# 2layer_v2.net
KiCad netlist of a schematic drawn in EAGLE
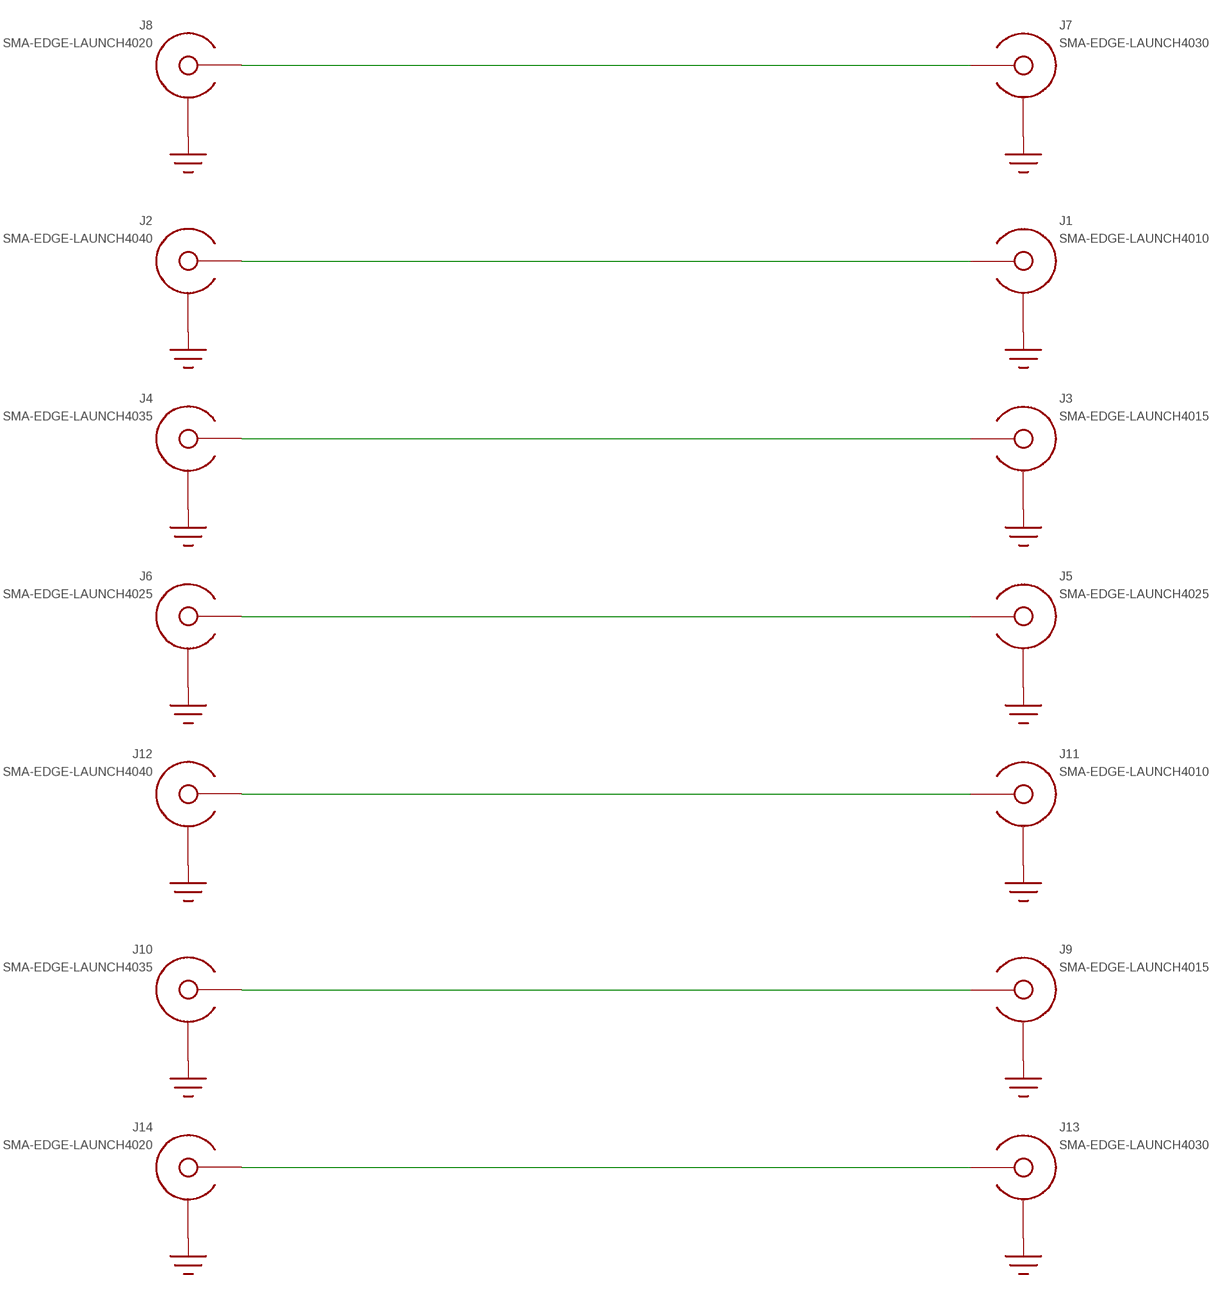
[diagram p0: schematic, sheet 1]

(export (version "E")
  (design (tool "Eeschema 10.0.6"))
  (components
    (comp (ref "J1")
      (value "SMA-EDGE-LAUNCH4010")
      (footprint "eagle-import:SMA_EDGE_LAUNCH_2L_4010")
      (libsource (lib "eagle-import") (part "SMA-EDGE-LAUNCH4010"))
    )
    (comp (ref "J2")
      (value "SMA-EDGE-LAUNCH4040")
      (footprint "eagle-import:SMA_EDGE_LAUNCH_2L_4040")
      (libsource (lib "eagle-import") (part "SMA-EDGE-LAUNCH4040"))
    )
    (comp (ref "J3")
      (value "SMA-EDGE-LAUNCH4015")
      (footprint "eagle-import:SMA_EDGE_LAUNCH_2L_4015")
      (libsource (lib "eagle-import") (part "SMA-EDGE-LAUNCH4015"))
    )
    (comp (ref "J4")
      (value "SMA-EDGE-LAUNCH4035")
      (footprint "eagle-import:SMA_EDGE_LAUNCH_2L_4035")
      (libsource (lib "eagle-import") (part "SMA-EDGE-LAUNCH4035"))
    )
    (comp (ref "J5")
      (value "SMA-EDGE-LAUNCH4025")
      (footprint "eagle-import:SMA_EDGE_LAUNCH_2L_4025")
      (libsource (lib "eagle-import") (part "SMA-EDGE-LAUNCH4025"))
    )
    (comp (ref "J6")
      (value "SMA-EDGE-LAUNCH4025")
      (footprint "eagle-import:SMA_EDGE_LAUNCH_2L_4025")
      (libsource (lib "eagle-import") (part "SMA-EDGE-LAUNCH4025"))
    )
    (comp (ref "J7")
      (value "SMA-EDGE-LAUNCH4030")
      (footprint "eagle-import:SMA_EDGE_LAUNCH_2L_4030")
      (libsource (lib "eagle-import") (part "SMA-EDGE-LAUNCH4030"))
    )
    (comp (ref "J8")
      (value "SMA-EDGE-LAUNCH4020")
      (footprint "eagle-import:SMA_EDGE_LAUNCH_2L_4020")
      (libsource (lib "eagle-import") (part "SMA-EDGE-LAUNCH4020"))
    )
    (comp (ref "J9")
      (value "SMA-EDGE-LAUNCH4015")
      (footprint "eagle-import:SMA_EDGE_LAUNCH_2L_4015")
      (libsource (lib "eagle-import") (part "SMA-EDGE-LAUNCH4015"))
    )
    (comp (ref "J10")
      (value "SMA-EDGE-LAUNCH4035")
      (footprint "eagle-import:SMA_EDGE_LAUNCH_2L_4035")
      (libsource (lib "eagle-import") (part "SMA-EDGE-LAUNCH4035"))
    )
    (comp (ref "J11")
      (value "SMA-EDGE-LAUNCH4010")
      (footprint "eagle-import:SMA_EDGE_LAUNCH_2L_4010")
      (libsource (lib "eagle-import") (part "SMA-EDGE-LAUNCH4010"))
    )
    (comp (ref "J12")
      (value "SMA-EDGE-LAUNCH4040")
      (footprint "eagle-import:SMA_EDGE_LAUNCH_2L_4040")
      (libsource (lib "eagle-import") (part "SMA-EDGE-LAUNCH4040"))
    )
    (comp (ref "J13")
      (value "SMA-EDGE-LAUNCH4030")
      (footprint "eagle-import:SMA_EDGE_LAUNCH_2L_4030")
      (libsource (lib "eagle-import") (part "SMA-EDGE-LAUNCH4030"))
    )
    (comp (ref "J14")
      (value "SMA-EDGE-LAUNCH4020")
      (footprint "eagle-import:SMA_EDGE_LAUNCH_2L_4020")
      (libsource (lib "eagle-import") (part "SMA-EDGE-LAUNCH4020"))
    )
  )
  (nets
    (net (code "1") (name "GND") (class "Default")
      (node (ref "J1") (pin "BOTTOM_GND") (pinfunction "SHIELD_BOTTOM_GND") (pintype "bidirectional"))
      (node (ref "J1") (pin "GND@1") (pinfunction "SHIELD_GND@1") (pintype "bidirectional"))
      (node (ref "J1") (pin "GND@11") (pinfunction "SHIELD_GND@11") (pintype "bidirectional"))
      (node (ref "J1") (pin "GND@12") (pinfunction "SHIELD_GND@12") (pintype "bidirectional"))
      (node (ref "J1") (pin "GND@14") (pinfunction "SHIELD_GND@14") (pintype "bidirectional"))
      (node (ref "J1") (pin "GND@15") (pinfunction "SHIELD_GND@15") (pintype "bidirectional"))
      (node (ref "J1") (pin "GND@16") (pinfunction "SHIELD_GND@16") (pintype "bidirectional"))
      (node (ref "J1") (pin "GND@17") (pinfunction "SHIELD_GND@17") (pintype "bidirectional"))
      (node (ref "J1") (pin "GND@2") (pinfunction "SHIELD_GND@2") (pintype "bidirectional"))
      (node (ref "J1") (pin "GND@3") (pinfunction "SHIELD_GND@3") (pintype "bidirectional"))
      (node (ref "J1") (pin "GND@4") (pinfunction "SHIELD_GND@4") (pintype "bidirectional"))
      (node (ref "J1") (pin "GND@5") (pinfunction "SHIELD_GND@5") (pintype "bidirectional"))
      (node (ref "J1") (pin "GND@6") (pinfunction "SHIELD_GND@6") (pintype "bidirectional"))
      (node (ref "J1") (pin "GND@7") (pinfunction "SHIELD_GND@7") (pintype "bidirectional"))
      (node (ref "J1") (pin "GND@8") (pinfunction "SHIELD_GND@8") (pintype "bidirectional"))
      (node (ref "J1") (pin "GND_PAD1") (pinfunction "SHIELD_GND_PAD1") (pintype "bidirectional"))
      (node (ref "J1") (pin "GND_PAD2") (pinfunction "SHIELD_GND_PAD2") (pintype "bidirectional"))
      (node (ref "J10") (pin "BOTTOM_GND") (pinfunction "SHIELD_BOTTOM_GND") (pintype "bidirectional"))
      (node (ref "J10") (pin "GND@1") (pinfunction "SHIELD_GND@1") (pintype "bidirectional"))
      (node (ref "J10") (pin "GND@11") (pinfunction "SHIELD_GND@11") (pintype "bidirectional"))
      (node (ref "J10") (pin "GND@12") (pinfunction "SHIELD_GND@12") (pintype "bidirectional"))
      (node (ref "J10") (pin "GND@14") (pinfunction "SHIELD_GND@14") (pintype "bidirectional"))
      (node (ref "J10") (pin "GND@15") (pinfunction "SHIELD_GND@15") (pintype "bidirectional"))
      (node (ref "J10") (pin "GND@16") (pinfunction "SHIELD_GND@16") (pintype "bidirectional"))
      (node (ref "J10") (pin "GND@17") (pinfunction "SHIELD_GND@17") (pintype "bidirectional"))
      (node (ref "J10") (pin "GND@2") (pinfunction "SHIELD_GND@2") (pintype "bidirectional"))
      (node (ref "J10") (pin "GND@3") (pinfunction "SHIELD_GND@3") (pintype "bidirectional"))
      (node (ref "J10") (pin "GND@4") (pinfunction "SHIELD_GND@4") (pintype "bidirectional"))
      (node (ref "J10") (pin "GND@5") (pinfunction "SHIELD_GND@5") (pintype "bidirectional"))
      (node (ref "J10") (pin "GND@6") (pinfunction "SHIELD_GND@6") (pintype "bidirectional"))
      (node (ref "J10") (pin "GND@7") (pinfunction "SHIELD_GND@7") (pintype "bidirectional"))
      (node (ref "J10") (pin "GND@8") (pinfunction "SHIELD_GND@8") (pintype "bidirectional"))
      (node (ref "J10") (pin "GND_PAD1") (pinfunction "SHIELD_GND_PAD1") (pintype "bidirectional"))
      (node (ref "J10") (pin "GND_PAD2") (pinfunction "SHIELD_GND_PAD2") (pintype "bidirectional"))
      (node (ref "J11") (pin "BOTTOM_GND") (pinfunction "SHIELD_BOTTOM_GND") (pintype "bidirectional"))
      (node (ref "J11") (pin "GND@1") (pinfunction "SHIELD_GND@1") (pintype "bidirectional"))
      (node (ref "J11") (pin "GND@11") (pinfunction "SHIELD_GND@11") (pintype "bidirectional"))
      (node (ref "J11") (pin "GND@12") (pinfunction "SHIELD_GND@12") (pintype "bidirectional"))
      (node (ref "J11") (pin "GND@14") (pinfunction "SHIELD_GND@14") (pintype "bidirectional"))
      (node (ref "J11") (pin "GND@15") (pinfunction "SHIELD_GND@15") (pintype "bidirectional"))
      (node (ref "J11") (pin "GND@16") (pinfunction "SHIELD_GND@16") (pintype "bidirectional"))
      (node (ref "J11") (pin "GND@17") (pinfunction "SHIELD_GND@17") (pintype "bidirectional"))
      (node (ref "J11") (pin "GND@2") (pinfunction "SHIELD_GND@2") (pintype "bidirectional"))
      (node (ref "J11") (pin "GND@3") (pinfunction "SHIELD_GND@3") (pintype "bidirectional"))
      (node (ref "J11") (pin "GND@4") (pinfunction "SHIELD_GND@4") (pintype "bidirectional"))
      (node (ref "J11") (pin "GND@5") (pinfunction "SHIELD_GND@5") (pintype "bidirectional"))
      (node (ref "J11") (pin "GND@6") (pinfunction "SHIELD_GND@6") (pintype "bidirectional"))
      (node (ref "J11") (pin "GND@7") (pinfunction "SHIELD_GND@7") (pintype "bidirectional"))
      (node (ref "J11") (pin "GND@8") (pinfunction "SHIELD_GND@8") (pintype "bidirectional"))
      (node (ref "J11") (pin "GND_PAD1") (pinfunction "SHIELD_GND_PAD1") (pintype "bidirectional"))
      (node (ref "J11") (pin "GND_PAD2") (pinfunction "SHIELD_GND_PAD2") (pintype "bidirectional"))
      (node (ref "J12") (pin "BOTTOM_GND") (pinfunction "SHIELD_BOTTOM_GND") (pintype "bidirectional"))
      (node (ref "J12") (pin "GND@1") (pinfunction "SHIELD_GND@1") (pintype "bidirectional"))
      (node (ref "J12") (pin "GND@11") (pinfunction "SHIELD_GND@11") (pintype "bidirectional"))
      (node (ref "J12") (pin "GND@12") (pinfunction "SHIELD_GND@12") (pintype "bidirectional"))
      (node (ref "J12") (pin "GND@14") (pinfunction "SHIELD_GND@14") (pintype "bidirectional"))
      (node (ref "J12") (pin "GND@15") (pinfunction "SHIELD_GND@15") (pintype "bidirectional"))
      (node (ref "J12") (pin "GND@16") (pinfunction "SHIELD_GND@16") (pintype "bidirectional"))
      (node (ref "J12") (pin "GND@17") (pinfunction "SHIELD_GND@17") (pintype "bidirectional"))
      (node (ref "J12") (pin "GND@2") (pinfunction "SHIELD_GND@2") (pintype "bidirectional"))
      (node (ref "J12") (pin "GND@3") (pinfunction "SHIELD_GND@3") (pintype "bidirectional"))
      (node (ref "J12") (pin "GND@4") (pinfunction "SHIELD_GND@4") (pintype "bidirectional"))
      (node (ref "J12") (pin "GND@5") (pinfunction "SHIELD_GND@5") (pintype "bidirectional"))
      (node (ref "J12") (pin "GND@6") (pinfunction "SHIELD_GND@6") (pintype "bidirectional"))
      (node (ref "J12") (pin "GND@7") (pinfunction "SHIELD_GND@7") (pintype "bidirectional"))
      (node (ref "J12") (pin "GND@8") (pinfunction "SHIELD_GND@8") (pintype "bidirectional"))
      (node (ref "J12") (pin "GND_PAD1") (pinfunction "SHIELD_GND_PAD1") (pintype "bidirectional"))
      (node (ref "J12") (pin "GND_PAD2") (pinfunction "SHIELD_GND_PAD2") (pintype "bidirectional"))
      (node (ref "J13") (pin "BOTTOM_GND") (pinfunction "SHIELD_BOTTOM_GND") (pintype "bidirectional"))
      (node (ref "J13") (pin "GND@1") (pinfunction "SHIELD_GND@1") (pintype "bidirectional"))
      (node (ref "J13") (pin "GND@11") (pinfunction "SHIELD_GND@11") (pintype "bidirectional"))
      (node (ref "J13") (pin "GND@12") (pinfunction "SHIELD_GND@12") (pintype "bidirectional"))
      (node (ref "J13") (pin "GND@14") (pinfunction "SHIELD_GND@14") (pintype "bidirectional"))
      (node (ref "J13") (pin "GND@15") (pinfunction "SHIELD_GND@15") (pintype "bidirectional"))
      (node (ref "J13") (pin "GND@16") (pinfunction "SHIELD_GND@16") (pintype "bidirectional"))
      (node (ref "J13") (pin "GND@17") (pinfunction "SHIELD_GND@17") (pintype "bidirectional"))
      (node (ref "J13") (pin "GND@2") (pinfunction "SHIELD_GND@2") (pintype "bidirectional"))
      (node (ref "J13") (pin "GND@3") (pinfunction "SHIELD_GND@3") (pintype "bidirectional"))
      (node (ref "J13") (pin "GND@4") (pinfunction "SHIELD_GND@4") (pintype "bidirectional"))
      (node (ref "J13") (pin "GND@5") (pinfunction "SHIELD_GND@5") (pintype "bidirectional"))
      (node (ref "J13") (pin "GND@6") (pinfunction "SHIELD_GND@6") (pintype "bidirectional"))
      (node (ref "J13") (pin "GND@7") (pinfunction "SHIELD_GND@7") (pintype "bidirectional"))
      (node (ref "J13") (pin "GND@8") (pinfunction "SHIELD_GND@8") (pintype "bidirectional"))
      (node (ref "J13") (pin "GND_PAD1") (pinfunction "SHIELD_GND_PAD1") (pintype "bidirectional"))
      (node (ref "J13") (pin "GND_PAD2") (pinfunction "SHIELD_GND_PAD2") (pintype "bidirectional"))
      (node (ref "J14") (pin "BOTTOM_GND") (pinfunction "SHIELD_BOTTOM_GND") (pintype "bidirectional"))
      (node (ref "J14") (pin "GND@1") (pinfunction "SHIELD_GND@1") (pintype "bidirectional"))
      (node (ref "J14") (pin "GND@11") (pinfunction "SHIELD_GND@11") (pintype "bidirectional"))
      (node (ref "J14") (pin "GND@12") (pinfunction "SHIELD_GND@12") (pintype "bidirectional"))
      (node (ref "J14") (pin "GND@14") (pinfunction "SHIELD_GND@14") (pintype "bidirectional"))
      (node (ref "J14") (pin "GND@15") (pinfunction "SHIELD_GND@15") (pintype "bidirectional"))
      (node (ref "J14") (pin "GND@16") (pinfunction "SHIELD_GND@16") (pintype "bidirectional"))
      (node (ref "J14") (pin "GND@17") (pinfunction "SHIELD_GND@17") (pintype "bidirectional"))
      (node (ref "J14") (pin "GND@2") (pinfunction "SHIELD_GND@2") (pintype "bidirectional"))
      (node (ref "J14") (pin "GND@3") (pinfunction "SHIELD_GND@3") (pintype "bidirectional"))
      (node (ref "J14") (pin "GND@4") (pinfunction "SHIELD_GND@4") (pintype "bidirectional"))
      (node (ref "J14") (pin "GND@5") (pinfunction "SHIELD_GND@5") (pintype "bidirectional"))
      (node (ref "J14") (pin "GND@6") (pinfunction "SHIELD_GND@6") (pintype "bidirectional"))
      (node (ref "J14") (pin "GND@7") (pinfunction "SHIELD_GND@7") (pintype "bidirectional"))
      (node (ref "J14") (pin "GND@8") (pinfunction "SHIELD_GND@8") (pintype "bidirectional"))
      (node (ref "J14") (pin "GND_PAD1") (pinfunction "SHIELD_GND_PAD1") (pintype "bidirectional"))
      (node (ref "J14") (pin "GND_PAD2") (pinfunction "SHIELD_GND_PAD2") (pintype "bidirectional"))
      (node (ref "J2") (pin "BOTTOM_GND") (pinfunction "SHIELD_BOTTOM_GND") (pintype "bidirectional"))
      (node (ref "J2") (pin "GND@1") (pinfunction "SHIELD_GND@1") (pintype "bidirectional"))
      (node (ref "J2") (pin "GND@11") (pinfunction "SHIELD_GND@11") (pintype "bidirectional"))
      (node (ref "J2") (pin "GND@12") (pinfunction "SHIELD_GND@12") (pintype "bidirectional"))
      (node (ref "J2") (pin "GND@14") (pinfunction "SHIELD_GND@14") (pintype "bidirectional"))
      (node (ref "J2") (pin "GND@15") (pinfunction "SHIELD_GND@15") (pintype "bidirectional"))
      (node (ref "J2") (pin "GND@16") (pinfunction "SHIELD_GND@16") (pintype "bidirectional"))
      (node (ref "J2") (pin "GND@17") (pinfunction "SHIELD_GND@17") (pintype "bidirectional"))
      (node (ref "J2") (pin "GND@2") (pinfunction "SHIELD_GND@2") (pintype "bidirectional"))
      (node (ref "J2") (pin "GND@3") (pinfunction "SHIELD_GND@3") (pintype "bidirectional"))
      (node (ref "J2") (pin "GND@4") (pinfunction "SHIELD_GND@4") (pintype "bidirectional"))
      (node (ref "J2") (pin "GND@5") (pinfunction "SHIELD_GND@5") (pintype "bidirectional"))
      (node (ref "J2") (pin "GND@6") (pinfunction "SHIELD_GND@6") (pintype "bidirectional"))
      (node (ref "J2") (pin "GND@7") (pinfunction "SHIELD_GND@7") (pintype "bidirectional"))
      (node (ref "J2") (pin "GND@8") (pinfunction "SHIELD_GND@8") (pintype "bidirectional"))
      (node (ref "J2") (pin "GND_PAD1") (pinfunction "SHIELD_GND_PAD1") (pintype "bidirectional"))
      (node (ref "J2") (pin "GND_PAD2") (pinfunction "SHIELD_GND_PAD2") (pintype "bidirectional"))
      (node (ref "J3") (pin "BOTTOM_GND") (pinfunction "SHIELD_BOTTOM_GND") (pintype "bidirectional"))
      (node (ref "J3") (pin "GND@1") (pinfunction "SHIELD_GND@1") (pintype "bidirectional"))
      (node (ref "J3") (pin "GND@11") (pinfunction "SHIELD_GND@11") (pintype "bidirectional"))
      (node (ref "J3") (pin "GND@12") (pinfunction "SHIELD_GND@12") (pintype "bidirectional"))
      (node (ref "J3") (pin "GND@14") (pinfunction "SHIELD_GND@14") (pintype "bidirectional"))
      (node (ref "J3") (pin "GND@15") (pinfunction "SHIELD_GND@15") (pintype "bidirectional"))
      (node (ref "J3") (pin "GND@16") (pinfunction "SHIELD_GND@16") (pintype "bidirectional"))
      (node (ref "J3") (pin "GND@17") (pinfunction "SHIELD_GND@17") (pintype "bidirectional"))
      (node (ref "J3") (pin "GND@2") (pinfunction "SHIELD_GND@2") (pintype "bidirectional"))
      (node (ref "J3") (pin "GND@3") (pinfunction "SHIELD_GND@3") (pintype "bidirectional"))
      (node (ref "J3") (pin "GND@4") (pinfunction "SHIELD_GND@4") (pintype "bidirectional"))
      (node (ref "J3") (pin "GND@5") (pinfunction "SHIELD_GND@5") (pintype "bidirectional"))
      (node (ref "J3") (pin "GND@6") (pinfunction "SHIELD_GND@6") (pintype "bidirectional"))
      (node (ref "J3") (pin "GND@7") (pinfunction "SHIELD_GND@7") (pintype "bidirectional"))
      (node (ref "J3") (pin "GND@8") (pinfunction "SHIELD_GND@8") (pintype "bidirectional"))
      (node (ref "J3") (pin "GND_PAD1") (pinfunction "SHIELD_GND_PAD1") (pintype "bidirectional"))
      (node (ref "J3") (pin "GND_PAD2") (pinfunction "SHIELD_GND_PAD2") (pintype "bidirectional"))
      (node (ref "J4") (pin "BOTTOM_GND") (pinfunction "SHIELD_BOTTOM_GND") (pintype "bidirectional"))
      (node (ref "J4") (pin "GND@1") (pinfunction "SHIELD_GND@1") (pintype "bidirectional"))
      (node (ref "J4") (pin "GND@11") (pinfunction "SHIELD_GND@11") (pintype "bidirectional"))
      (node (ref "J4") (pin "GND@12") (pinfunction "SHIELD_GND@12") (pintype "bidirectional"))
      (node (ref "J4") (pin "GND@14") (pinfunction "SHIELD_GND@14") (pintype "bidirectional"))
      (node (ref "J4") (pin "GND@15") (pinfunction "SHIELD_GND@15") (pintype "bidirectional"))
      (node (ref "J4") (pin "GND@16") (pinfunction "SHIELD_GND@16") (pintype "bidirectional"))
      (node (ref "J4") (pin "GND@17") (pinfunction "SHIELD_GND@17") (pintype "bidirectional"))
      (node (ref "J4") (pin "GND@2") (pinfunction "SHIELD_GND@2") (pintype "bidirectional"))
      (node (ref "J4") (pin "GND@3") (pinfunction "SHIELD_GND@3") (pintype "bidirectional"))
      (node (ref "J4") (pin "GND@4") (pinfunction "SHIELD_GND@4") (pintype "bidirectional"))
      (node (ref "J4") (pin "GND@5") (pinfunction "SHIELD_GND@5") (pintype "bidirectional"))
      (node (ref "J4") (pin "GND@6") (pinfunction "SHIELD_GND@6") (pintype "bidirectional"))
      (node (ref "J4") (pin "GND@7") (pinfunction "SHIELD_GND@7") (pintype "bidirectional"))
      (node (ref "J4") (pin "GND@8") (pinfunction "SHIELD_GND@8") (pintype "bidirectional"))
      (node (ref "J4") (pin "GND_PAD1") (pinfunction "SHIELD_GND_PAD1") (pintype "bidirectional"))
      (node (ref "J4") (pin "GND_PAD2") (pinfunction "SHIELD_GND_PAD2") (pintype "bidirectional"))
      (node (ref "J5") (pin "BOTTOM_GND") (pinfunction "SHIELD_BOTTOM_GND") (pintype "bidirectional"))
      (node (ref "J5") (pin "GND@1") (pinfunction "SHIELD_GND@1") (pintype "bidirectional"))
      (node (ref "J5") (pin "GND@11") (pinfunction "SHIELD_GND@11") (pintype "bidirectional"))
      (node (ref "J5") (pin "GND@12") (pinfunction "SHIELD_GND@12") (pintype "bidirectional"))
      (node (ref "J5") (pin "GND@14") (pinfunction "SHIELD_GND@14") (pintype "bidirectional"))
      (node (ref "J5") (pin "GND@15") (pinfunction "SHIELD_GND@15") (pintype "bidirectional"))
      (node (ref "J5") (pin "GND@16") (pinfunction "SHIELD_GND@16") (pintype "bidirectional"))
      (node (ref "J5") (pin "GND@17") (pinfunction "SHIELD_GND@17") (pintype "bidirectional"))
      (node (ref "J5") (pin "GND@2") (pinfunction "SHIELD_GND@2") (pintype "bidirectional"))
      (node (ref "J5") (pin "GND@3") (pinfunction "SHIELD_GND@3") (pintype "bidirectional"))
      (node (ref "J5") (pin "GND@4") (pinfunction "SHIELD_GND@4") (pintype "bidirectional"))
      (node (ref "J5") (pin "GND@5") (pinfunction "SHIELD_GND@5") (pintype "bidirectional"))
      (node (ref "J5") (pin "GND@6") (pinfunction "SHIELD_GND@6") (pintype "bidirectional"))
      (node (ref "J5") (pin "GND@7") (pinfunction "SHIELD_GND@7") (pintype "bidirectional"))
      (node (ref "J5") (pin "GND@8") (pinfunction "SHIELD_GND@8") (pintype "bidirectional"))
      (node (ref "J5") (pin "GND_PAD1") (pinfunction "SHIELD_GND_PAD1") (pintype "bidirectional"))
      (node (ref "J5") (pin "GND_PAD2") (pinfunction "SHIELD_GND_PAD2") (pintype "bidirectional"))
      (node (ref "J6") (pin "BOTTOM_GND") (pinfunction "SHIELD_BOTTOM_GND") (pintype "bidirectional"))
      (node (ref "J6") (pin "GND@1") (pinfunction "SHIELD_GND@1") (pintype "bidirectional"))
      (node (ref "J6") (pin "GND@11") (pinfunction "SHIELD_GND@11") (pintype "bidirectional"))
      (node (ref "J6") (pin "GND@12") (pinfunction "SHIELD_GND@12") (pintype "bidirectional"))
      (node (ref "J6") (pin "GND@14") (pinfunction "SHIELD_GND@14") (pintype "bidirectional"))
      (node (ref "J6") (pin "GND@15") (pinfunction "SHIELD_GND@15") (pintype "bidirectional"))
      (node (ref "J6") (pin "GND@16") (pinfunction "SHIELD_GND@16") (pintype "bidirectional"))
      (node (ref "J6") (pin "GND@17") (pinfunction "SHIELD_GND@17") (pintype "bidirectional"))
      (node (ref "J6") (pin "GND@2") (pinfunction "SHIELD_GND@2") (pintype "bidirectional"))
      (node (ref "J6") (pin "GND@3") (pinfunction "SHIELD_GND@3") (pintype "bidirectional"))
      (node (ref "J6") (pin "GND@4") (pinfunction "SHIELD_GND@4") (pintype "bidirectional"))
      (node (ref "J6") (pin "GND@5") (pinfunction "SHIELD_GND@5") (pintype "bidirectional"))
      (node (ref "J6") (pin "GND@6") (pinfunction "SHIELD_GND@6") (pintype "bidirectional"))
      (node (ref "J6") (pin "GND@7") (pinfunction "SHIELD_GND@7") (pintype "bidirectional"))
      (node (ref "J6") (pin "GND@8") (pinfunction "SHIELD_GND@8") (pintype "bidirectional"))
      (node (ref "J6") (pin "GND_PAD1") (pinfunction "SHIELD_GND_PAD1") (pintype "bidirectional"))
      (node (ref "J6") (pin "GND_PAD2") (pinfunction "SHIELD_GND_PAD2") (pintype "bidirectional"))
      (node (ref "J7") (pin "BOTTOM_GND") (pinfunction "SHIELD_BOTTOM_GND") (pintype "bidirectional"))
      (node (ref "J7") (pin "GND@1") (pinfunction "SHIELD_GND@1") (pintype "bidirectional"))
      (node (ref "J7") (pin "GND@11") (pinfunction "SHIELD_GND@11") (pintype "bidirectional"))
      (node (ref "J7") (pin "GND@12") (pinfunction "SHIELD_GND@12") (pintype "bidirectional"))
      (node (ref "J7") (pin "GND@14") (pinfunction "SHIELD_GND@14") (pintype "bidirectional"))
      (node (ref "J7") (pin "GND@15") (pinfunction "SHIELD_GND@15") (pintype "bidirectional"))
      (node (ref "J7") (pin "GND@16") (pinfunction "SHIELD_GND@16") (pintype "bidirectional"))
      (node (ref "J7") (pin "GND@17") (pinfunction "SHIELD_GND@17") (pintype "bidirectional"))
      (node (ref "J7") (pin "GND@2") (pinfunction "SHIELD_GND@2") (pintype "bidirectional"))
      (node (ref "J7") (pin "GND@3") (pinfunction "SHIELD_GND@3") (pintype "bidirectional"))
      (node (ref "J7") (pin "GND@4") (pinfunction "SHIELD_GND@4") (pintype "bidirectional"))
      (node (ref "J7") (pin "GND@5") (pinfunction "SHIELD_GND@5") (pintype "bidirectional"))
      (node (ref "J7") (pin "GND@6") (pinfunction "SHIELD_GND@6") (pintype "bidirectional"))
      (node (ref "J7") (pin "GND@7") (pinfunction "SHIELD_GND@7") (pintype "bidirectional"))
      (node (ref "J7") (pin "GND@8") (pinfunction "SHIELD_GND@8") (pintype "bidirectional"))
      (node (ref "J7") (pin "GND_PAD1") (pinfunction "SHIELD_GND_PAD1") (pintype "bidirectional"))
      (node (ref "J7") (pin "GND_PAD2") (pinfunction "SHIELD_GND_PAD2") (pintype "bidirectional"))
      (node (ref "J8") (pin "BOTTOM_GND") (pinfunction "SHIELD_BOTTOM_GND") (pintype "bidirectional"))
      (node (ref "J8") (pin "GND@1") (pinfunction "SHIELD_GND@1") (pintype "bidirectional"))
      (node (ref "J8") (pin "GND@11") (pinfunction "SHIELD_GND@11") (pintype "bidirectional"))
      (node (ref "J8") (pin "GND@12") (pinfunction "SHIELD_GND@12") (pintype "bidirectional"))
      (node (ref "J8") (pin "GND@14") (pinfunction "SHIELD_GND@14") (pintype "bidirectional"))
      (node (ref "J8") (pin "GND@15") (pinfunction "SHIELD_GND@15") (pintype "bidirectional"))
      (node (ref "J8") (pin "GND@16") (pinfunction "SHIELD_GND@16") (pintype "bidirectional"))
      (node (ref "J8") (pin "GND@17") (pinfunction "SHIELD_GND@17") (pintype "bidirectional"))
      (node (ref "J8") (pin "GND@2") (pinfunction "SHIELD_GND@2") (pintype "bidirectional"))
      (node (ref "J8") (pin "GND@3") (pinfunction "SHIELD_GND@3") (pintype "bidirectional"))
      (node (ref "J8") (pin "GND@4") (pinfunction "SHIELD_GND@4") (pintype "bidirectional"))
      (node (ref "J8") (pin "GND@5") (pinfunction "SHIELD_GND@5") (pintype "bidirectional"))
      (node (ref "J8") (pin "GND@6") (pinfunction "SHIELD_GND@6") (pintype "bidirectional"))
      (node (ref "J8") (pin "GND@7") (pinfunction "SHIELD_GND@7") (pintype "bidirectional"))
      (node (ref "J8") (pin "GND@8") (pinfunction "SHIELD_GND@8") (pintype "bidirectional"))
      (node (ref "J8") (pin "GND_PAD1") (pinfunction "SHIELD_GND_PAD1") (pintype "bidirectional"))
      (node (ref "J8") (pin "GND_PAD2") (pinfunction "SHIELD_GND_PAD2") (pintype "bidirectional"))
      (node (ref "J9") (pin "BOTTOM_GND") (pinfunction "SHIELD_BOTTOM_GND") (pintype "bidirectional"))
      (node (ref "J9") (pin "GND@1") (pinfunction "SHIELD_GND@1") (pintype "bidirectional"))
      (node (ref "J9") (pin "GND@11") (pinfunction "SHIELD_GND@11") (pintype "bidirectional"))
      (node (ref "J9") (pin "GND@12") (pinfunction "SHIELD_GND@12") (pintype "bidirectional"))
      (node (ref "J9") (pin "GND@14") (pinfunction "SHIELD_GND@14") (pintype "bidirectional"))
      (node (ref "J9") (pin "GND@15") (pinfunction "SHIELD_GND@15") (pintype "bidirectional"))
      (node (ref "J9") (pin "GND@16") (pinfunction "SHIELD_GND@16") (pintype "bidirectional"))
      (node (ref "J9") (pin "GND@17") (pinfunction "SHIELD_GND@17") (pintype "bidirectional"))
      (node (ref "J9") (pin "GND@2") (pinfunction "SHIELD_GND@2") (pintype "bidirectional"))
      (node (ref "J9") (pin "GND@3") (pinfunction "SHIELD_GND@3") (pintype "bidirectional"))
      (node (ref "J9") (pin "GND@4") (pinfunction "SHIELD_GND@4") (pintype "bidirectional"))
      (node (ref "J9") (pin "GND@5") (pinfunction "SHIELD_GND@5") (pintype "bidirectional"))
      (node (ref "J9") (pin "GND@6") (pinfunction "SHIELD_GND@6") (pintype "bidirectional"))
      (node (ref "J9") (pin "GND@7") (pinfunction "SHIELD_GND@7") (pintype "bidirectional"))
      (node (ref "J9") (pin "GND@8") (pinfunction "SHIELD_GND@8") (pintype "bidirectional"))
      (node (ref "J9") (pin "GND_PAD1") (pinfunction "SHIELD_GND_PAD1") (pintype "bidirectional"))
      (node (ref "J9") (pin "GND_PAD2") (pinfunction "SHIELD_GND_PAD2") (pintype "bidirectional"))
    )
    (net (code "2") (name "Net-(J1-CENTER)") (class "Default")
      (node (ref "J1") (pin "CENTER@1") (pinfunction "CENTER_CENTER@1") (pintype "bidirectional"))
      (node (ref "J2") (pin "CENTER@1") (pinfunction "CENTER_CENTER@1") (pintype "bidirectional"))
    )
    (net (code "3") (name "Net-(J3-CENTER)") (class "Default")
      (node (ref "J3") (pin "CENTER@1") (pinfunction "CENTER_CENTER@1") (pintype "bidirectional"))
      (node (ref "J4") (pin "CENTER@1") (pinfunction "CENTER_CENTER@1") (pintype "bidirectional"))
    )
    (net (code "4") (name "Net-(J5-CENTER)") (class "Default")
      (node (ref "J5") (pin "CENTER@1") (pinfunction "CENTER_CENTER@1") (pintype "bidirectional"))
      (node (ref "J6") (pin "CENTER@1") (pinfunction "CENTER_CENTER@1") (pintype "bidirectional"))
    )
    (net (code "5") (name "Net-(J7-CENTER)") (class "Default")
      (node (ref "J7") (pin "CENTER@1") (pinfunction "CENTER_CENTER@1") (pintype "bidirectional"))
      (node (ref "J8") (pin "CENTER@1") (pinfunction "CENTER_CENTER@1") (pintype "bidirectional"))
    )
    (net (code "6") (name "Net-(J10-CENTER)") (class "Default")
      (node (ref "J10") (pin "CENTER@1") (pinfunction "CENTER_CENTER@1") (pintype "bidirectional"))
      (node (ref "J9") (pin "CENTER@1") (pinfunction "CENTER_CENTER@1") (pintype "bidirectional"))
    )
    (net (code "7") (name "Net-(J11-CENTER)") (class "Default")
      (node (ref "J11") (pin "CENTER@1") (pinfunction "CENTER_CENTER@1") (pintype "bidirectional"))
      (node (ref "J12") (pin "CENTER@1") (pinfunction "CENTER_CENTER@1") (pintype "bidirectional"))
    )
    (net (code "8") (name "Net-(J13-CENTER)") (class "Default")
      (node (ref "J13") (pin "CENTER@1") (pinfunction "CENTER_CENTER@1") (pintype "bidirectional"))
      (node (ref "J14") (pin "CENTER@1") (pinfunction "CENTER_CENTER@1") (pintype "bidirectional"))
    )
  )
)
